# HM-RC-8_Remote-v02-010.net
KiCad netlist of a schematic drawn in EAGLE
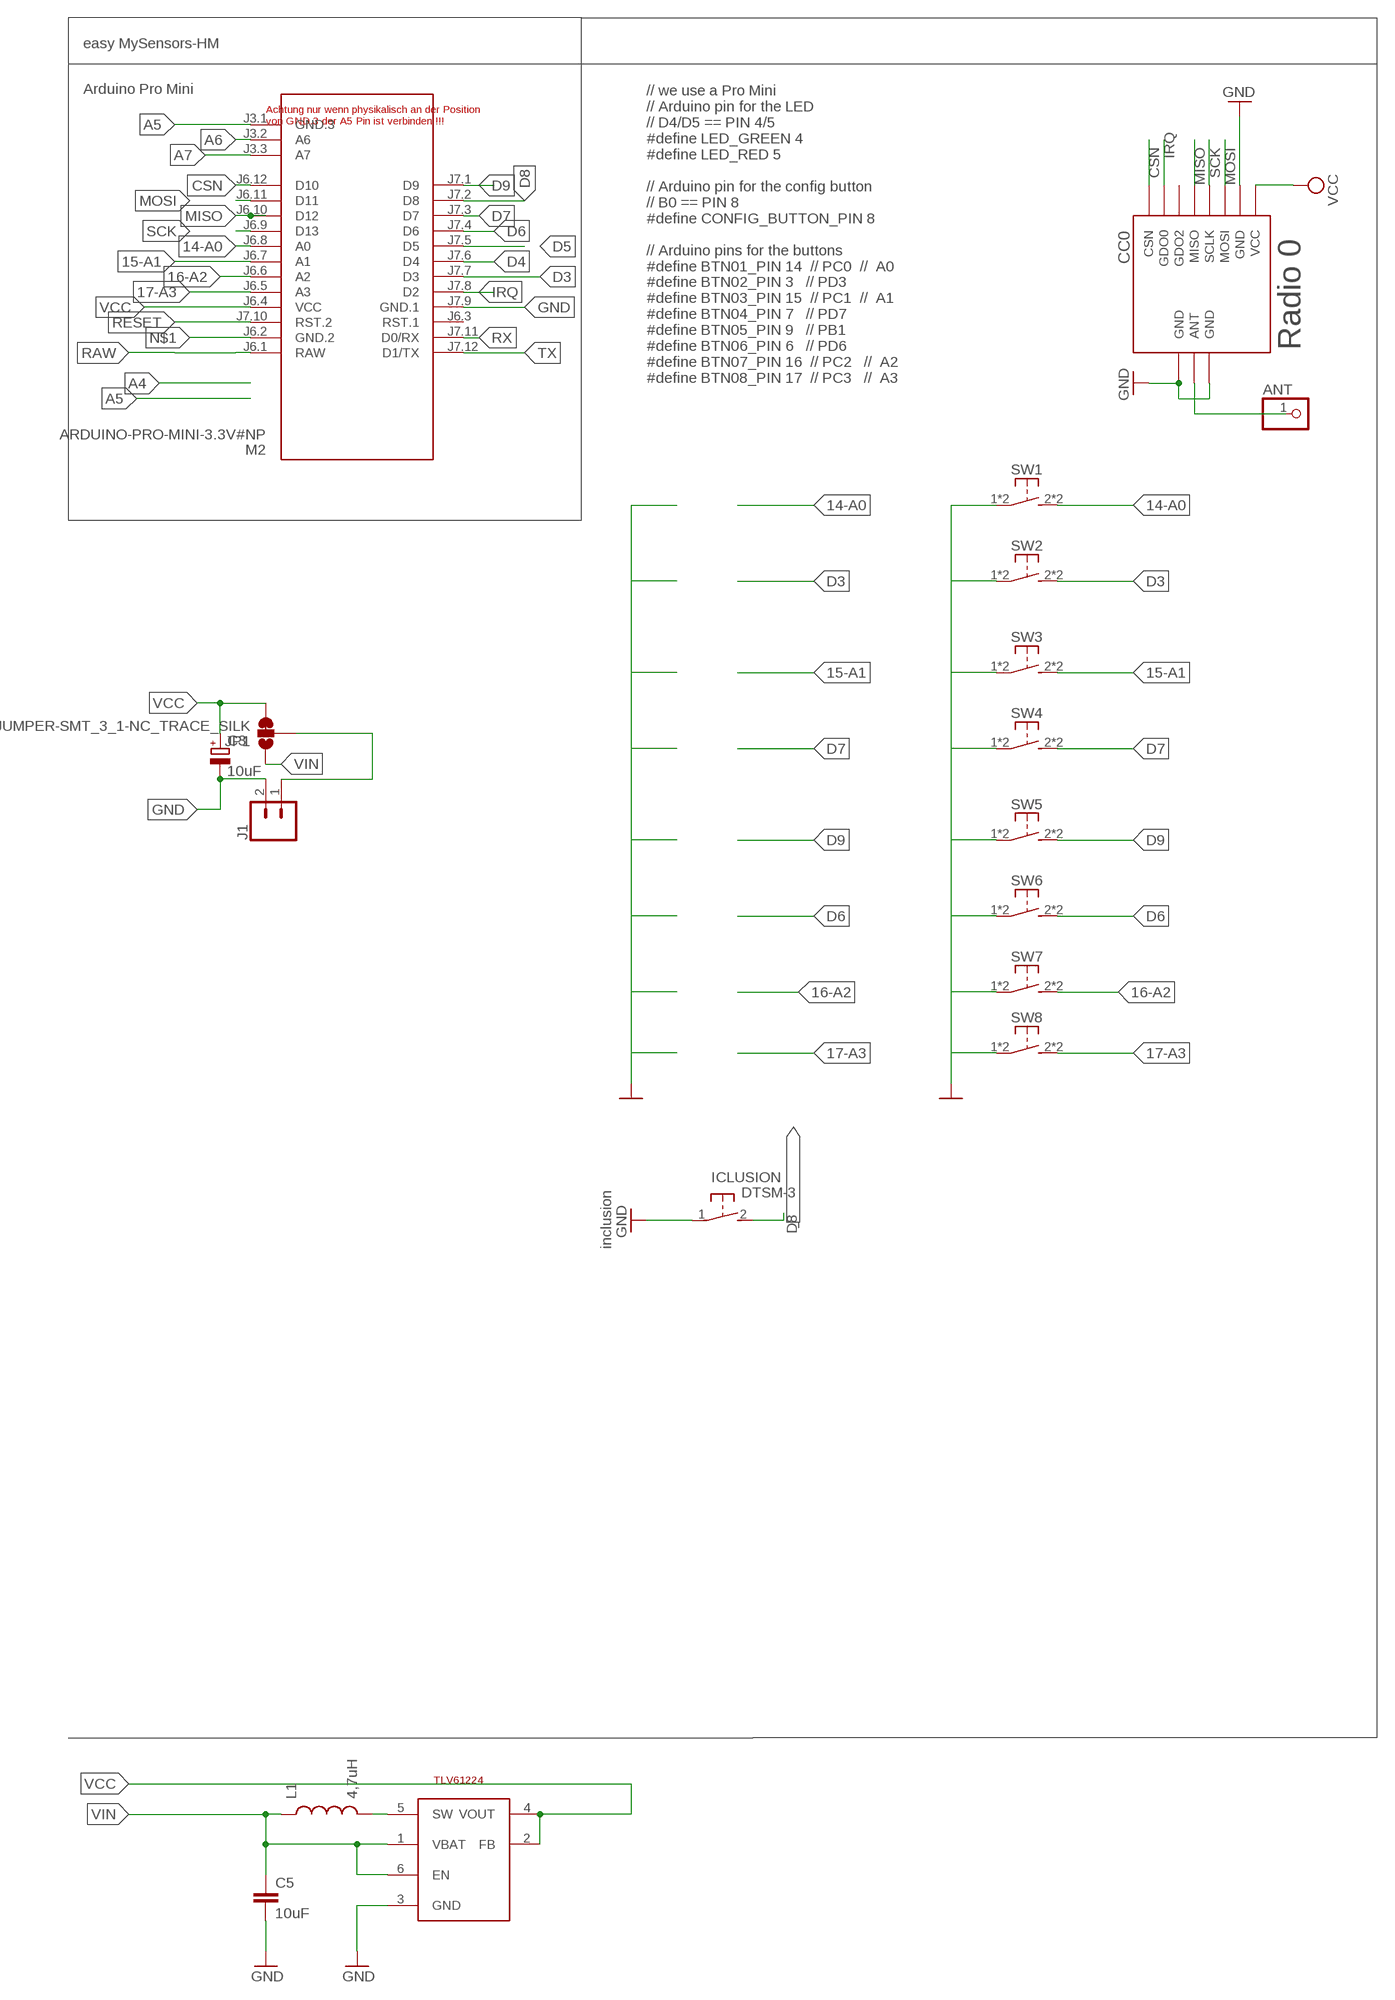
[diagram p0: schematic, sheet 1]

(export (version "E")
  (design (tool "Eeschema 10.0.6"))
  (components
    (comp (ref "ANT")
      (value "PINHD-1X1")
      (footprint "eagle-import:1X01")
      (libsource (lib "eagle-import") (part "PINHD-1X1"))
    )
    (comp (ref "C3")
      (value "10uF")
      (footprint "eagle-import:SMC_C")
      (libsource (lib "eagle-import") (part "CPOL-EUSMCC"))
    )
    (comp (ref "C5")
      (value "10uF")
      (footprint "eagle-import:0805")
      (libsource (lib "eagle-import") (part "CAP0805"))
    )
    (comp (ref "CC0")
      (value "CC1101")
      (footprint "eagle-import:CC1101_MODULE1_SMD")
      (libsource (lib "eagle-import") (part "CC1101_MODULE1SMD"))
    )
    (comp (ref "ICLUSION")
      (value "DTSM-3")
      (footprint "eagle-import:DTSM-3")
      (libsource (lib "eagle-import") (part "DTSM-3"))
    )
    (comp (ref "J1")
      (value "CONN_02PTH3")
      (footprint "eagle-import:1X02_LONGPADS")
      (libsource (lib "eagle-import") (part "CONN_02PTH3"))
    )
    (comp (ref "JP1")
      (value "JUMPER-SMT_3_1-NC_TRACE_SILK")
      (footprint "eagle-import:SMT-JUMPER_3_1-NC_TRACE_SILK")
      (libsource (lib "eagle-import") (part "JUMPER-SMT_3_1-NC_TRACE_SILK"))
    )
    (comp (ref "L1")
      (value "4,7uH")
      (footprint "eagle-import:0805")
      (libsource (lib "eagle-import") (part "INDUCTOR0805"))
    )
    (comp (ref "M2")
      (value "ARDUINO-PRO-MINI-3.3V#NP")
      (footprint "eagle-import:ARDUINO-PRO-MINI#NP")
      (libsource (lib "eagle-import") (part "ARDUINO-PRO-MINI-#NP3.3V"))
    )
    (comp (ref "STEPUP")
      (value "TLV61224")
      (footprint "eagle-import:SOT23-6L")
      (libsource (lib "eagle-import") (part "TI-TLV61224"))
    )
    (comp (ref "SW1")
      (value "SW-TACTILE-TL3305")
      (footprint "eagle-import:TL3305")
      (libsource (lib "eagle-import") (part "SW-TACTILE-TL3305"))
    )
    (comp (ref "SW2")
      (value "SW-TACTILE-TL3305")
      (footprint "eagle-import:TL3305")
      (libsource (lib "eagle-import") (part "SW-TACTILE-TL3305"))
    )
    (comp (ref "SW3")
      (value "SW-TACTILE-TL3305")
      (footprint "eagle-import:TL3305")
      (libsource (lib "eagle-import") (part "SW-TACTILE-TL3305"))
    )
    (comp (ref "SW4")
      (value "SW-TACTILE-TL3305")
      (footprint "eagle-import:TL3305")
      (libsource (lib "eagle-import") (part "SW-TACTILE-TL3305"))
    )
    (comp (ref "SW5")
      (value "SW-TACTILE-TL3305")
      (footprint "eagle-import:TL3305")
      (libsource (lib "eagle-import") (part "SW-TACTILE-TL3305"))
    )
    (comp (ref "SW6")
      (value "SW-TACTILE-TL3305")
      (footprint "eagle-import:TL3305")
      (libsource (lib "eagle-import") (part "SW-TACTILE-TL3305"))
    )
    (comp (ref "SW7")
      (value "SW-TACTILE-TL3305")
      (footprint "eagle-import:TL3305")
      (libsource (lib "eagle-import") (part "SW-TACTILE-TL3305"))
    )
    (comp (ref "SW8")
      (value "SW-TACTILE-TL3305")
      (footprint "eagle-import:TL3305")
      (libsource (lib "eagle-import") (part "SW-TACTILE-TL3305"))
    )
  )
  (nets
    (net (code "1") (name "14-A0") (class "Default")
      (node (ref "M2") (pin "J6.8") (pinfunction "A0_J6.8") (pintype "bidirectional"))
      (node (ref "SW1") (pin "2") (pinfunction "S1_2") (pintype "passive"))
      (node (ref "SW1") (pin "3") (pinfunction "S1_3") (pintype "passive"))
    )
    (net (code "2") (name "15-A1") (class "Default")
      (node (ref "M2") (pin "J6.7") (pinfunction "A1_J6.7") (pintype "bidirectional"))
      (node (ref "SW3") (pin "2") (pinfunction "S1_2") (pintype "passive"))
      (node (ref "SW3") (pin "3") (pinfunction "S1_3") (pintype "passive"))
    )
    (net (code "3") (name "16-A2") (class "Default")
      (node (ref "M2") (pin "J6.6") (pinfunction "A2_J6.6") (pintype "bidirectional"))
      (node (ref "SW7") (pin "2") (pinfunction "S1_2") (pintype "passive"))
      (node (ref "SW7") (pin "3") (pinfunction "S1_3") (pintype "passive"))
    )
    (net (code "4") (name "17-A3") (class "Default")
      (node (ref "M2") (pin "J6.5") (pinfunction "A3_J6.5") (pintype "bidirectional"))
      (node (ref "SW8") (pin "2") (pinfunction "S1_2") (pintype "passive"))
      (node (ref "SW8") (pin "3") (pinfunction "S1_3") (pintype "passive"))
    )
    (net (code "6") (name "A5") (class "Default")
      (node (ref "M2") (pin "J3.1") (pinfunction "GND.3_J3.1") (pintype "bidirectional"))
    )
    (net (code "7") (name "A6") (class "Default")
      (node (ref "M2") (pin "J3.2") (pinfunction "A6_J3.2") (pintype "bidirectional"))
    )
    (net (code "8") (name "A7") (class "Default")
      (node (ref "M2") (pin "J3.3") (pinfunction "A7_J3.3") (pintype "bidirectional"))
    )
    (net (code "9") (name "CSN") (class "Default")
      (node (ref "CC0") (pin "CSN") (pinfunction "CSN_CSN") (pintype "bidirectional"))
      (node (ref "M2") (pin "J6.12") (pinfunction "D10_J6.12") (pintype "bidirectional"))
    )
    (net (code "10") (name "D3") (class "Default")
      (node (ref "M2") (pin "J7.7") (pinfunction "D3_J7.7") (pintype "bidirectional"))
      (node (ref "SW2") (pin "2") (pinfunction "S1_2") (pintype "passive"))
      (node (ref "SW2") (pin "3") (pinfunction "S1_3") (pintype "passive"))
    )
    (net (code "11") (name "D4") (class "Default")
      (node (ref "M2") (pin "J7.6") (pinfunction "D4_J7.6") (pintype "bidirectional"))
    )
    (net (code "12") (name "D5") (class "Default")
      (node (ref "M2") (pin "J7.5") (pinfunction "D5_J7.5") (pintype "bidirectional"))
    )
    (net (code "13") (name "D6") (class "Default")
      (node (ref "M2") (pin "J7.4") (pinfunction "D6_J7.4") (pintype "bidirectional"))
      (node (ref "SW6") (pin "2") (pinfunction "S1_2") (pintype "passive"))
      (node (ref "SW6") (pin "3") (pinfunction "S1_3") (pintype "passive"))
    )
    (net (code "14") (name "D7") (class "Default")
      (node (ref "M2") (pin "J7.3") (pinfunction "D7_J7.3") (pintype "bidirectional"))
      (node (ref "SW4") (pin "2") (pinfunction "S1_2") (pintype "passive"))
      (node (ref "SW4") (pin "3") (pinfunction "S1_3") (pintype "passive"))
    )
    (net (code "15") (name "D8") (class "Default")
      (node (ref "ICLUSION") (pin "2") (pinfunction "2_2") (pintype "passive"))
      (node (ref "M2") (pin "J7.2") (pinfunction "D8_J7.2") (pintype "bidirectional"))
    )
    (net (code "16") (name "D9") (class "Default")
      (node (ref "M2") (pin "J7.1") (pinfunction "D9_J7.1") (pintype "bidirectional"))
      (node (ref "SW5") (pin "2") (pinfunction "S1_2") (pintype "passive"))
      (node (ref "SW5") (pin "3") (pinfunction "S1_3") (pintype "passive"))
    )
    (net (code "17") (name "GND") (class "Default")
      (node (ref "C3") (pin "-") (pinfunction "-_-") (pintype "passive"))
      (node (ref "C5") (pin "2") (pinfunction "2_2") (pintype "passive"))
      (node (ref "CC0") (pin "GND@0") (pinfunction "GND_GND@0") (pintype "power_in"))
      (node (ref "CC0") (pin "GND@1") (pinfunction "GND_GND@1") (pintype "power_in"))
      (node (ref "CC0") (pin "GND@2") (pinfunction "GND_GND@2") (pintype "power_in"))
      (node (ref "ICLUSION") (pin "1") (pinfunction "1_1") (pintype "passive"))
      (node (ref "J1") (pin "2") (pinfunction "2_2") (pintype "passive"))
      (node (ref "M2") (pin "J7.9") (pinfunction "GND.1_J7.9") (pintype "power_in"))
      (node (ref "STEPUP") (pin "3") (pinfunction "GND_3") (pintype "power_in"))
      (node (ref "SW1") (pin "1") (pinfunction "P1_1") (pintype "passive"))
      (node (ref "SW1") (pin "4") (pinfunction "P1_4") (pintype "passive"))
      (node (ref "SW3") (pin "1") (pinfunction "P1_1") (pintype "passive"))
      (node (ref "SW3") (pin "4") (pinfunction "P1_4") (pintype "passive"))
      (node (ref "SW4") (pin "1") (pinfunction "P1_1") (pintype "passive"))
      (node (ref "SW4") (pin "4") (pinfunction "P1_4") (pintype "passive"))
      (node (ref "SW5") (pin "1") (pinfunction "P1_1") (pintype "passive"))
      (node (ref "SW5") (pin "4") (pinfunction "P1_4") (pintype "passive"))
      (node (ref "SW6") (pin "1") (pinfunction "P1_1") (pintype "passive"))
      (node (ref "SW6") (pin "4") (pinfunction "P1_4") (pintype "passive"))
      (node (ref "SW7") (pin "1") (pinfunction "P1_1") (pintype "passive"))
      (node (ref "SW7") (pin "4") (pinfunction "P1_4") (pintype "passive"))
      (node (ref "SW8") (pin "1") (pinfunction "P1_1") (pintype "passive"))
      (node (ref "SW8") (pin "4") (pinfunction "P1_4") (pintype "passive"))
    )
    (net (code "18") (name "IRQ") (class "Default")
      (node (ref "CC0") (pin "GDO0") (pinfunction "GDO0_GDO0") (pintype "bidirectional"))
      (node (ref "M2") (pin "J7.8") (pinfunction "D2_J7.8") (pintype "bidirectional"))
    )
    (net (code "19") (name "MISO") (class "Default")
      (node (ref "CC0") (pin "MISO") (pinfunction "MISO_MISO") (pintype "bidirectional"))
      (node (ref "M2") (pin "J6.10") (pinfunction "D12_J6.10") (pintype "bidirectional"))
    )
    (net (code "20") (name "MOSI") (class "Default")
      (node (ref "CC0") (pin "MOSI") (pinfunction "MOSI_MOSI") (pintype "bidirectional"))
      (node (ref "M2") (pin "J6.11") (pinfunction "D11_J6.11") (pintype "bidirectional"))
    )
    (net (code "21") (name "N$1") (class "Default")
      (node (ref "M2") (pin "J6.2") (pinfunction "GND.2_J6.2") (pintype "power_in"))
    )
    (net (code "22") (name "Net-(ANT-Pad1)") (class "Default")
      (node (ref "ANT") (pin "1") (pinfunction "1_1") (pintype "passive"))
      (node (ref "CC0") (pin "ANT") (pinfunction "ANT_ANT") (pintype "output"))
    )
    (net (code "23") (name "Net-(J1-Pad1)") (class "Default")
      (node (ref "J1") (pin "1") (pinfunction "1_1") (pintype "passive"))
      (node (ref "JP1") (pin "2") (pinfunction "2_2") (pintype "passive"))
    )
    (net (code "24") (name "Net-(STEPUP-SW)") (class "Default")
      (node (ref "L1") (pin "2") (pinfunction "2_2") (pintype "passive"))
      (node (ref "STEPUP") (pin "5") (pinfunction "SW_5") (pintype "power_in"))
    )
    (net (code "25") (name "Net-(SW2-P1-Pad1)") (class "Default")
      (node (ref "SW2") (pin "1") (pinfunction "P1_1") (pintype "passive"))
      (node (ref "SW2") (pin "4") (pinfunction "P1_4") (pintype "passive"))
    )
    (net (code "26") (name "RAW") (class "Default")
      (node (ref "M2") (pin "J6.1") (pinfunction "RAW_J6.1") (pintype "power_in"))
    )
    (net (code "27") (name "RESET") (class "Default")
      (node (ref "M2") (pin "J7.10") (pinfunction "RST.2_J7.10") (pintype "bidirectional"))
    )
    (net (code "28") (name "RX") (class "Default")
      (node (ref "M2") (pin "J7.11") (pinfunction "D0/RX_J7.11") (pintype "bidirectional"))
    )
    (net (code "29") (name "SCK") (class "Default")
      (node (ref "CC0") (pin "SCLK") (pinfunction "SCLK_SCLK") (pintype "bidirectional"))
      (node (ref "M2") (pin "J6.9") (pinfunction "D13_J6.9") (pintype "bidirectional"))
    )
    (net (code "30") (name "TX") (class "Default")
      (node (ref "M2") (pin "J7.12") (pinfunction "D1/TX_J7.12") (pintype "bidirectional"))
    )
    (net (code "31") (name "VCC") (class "Default")
      (node (ref "C3") (pin "+") (pinfunction "+_+") (pintype "passive"))
      (node (ref "CC0") (pin "VCC") (pinfunction "VCC_VCC") (pintype "power_in"))
      (node (ref "JP1") (pin "3") (pinfunction "3_3") (pintype "passive"))
      (node (ref "M2") (pin "J6.4") (pinfunction "VCC_J6.4") (pintype "power_in"))
      (node (ref "STEPUP") (pin "2") (pinfunction "FB_2") (pintype "input"))
      (node (ref "STEPUP") (pin "4") (pinfunction "VOUT_4") (pintype "power_in"))
    )
    (net (code "32") (name "VIN") (class "Default")
      (node (ref "C5") (pin "1") (pinfunction "1_1") (pintype "passive"))
      (node (ref "JP1") (pin "1") (pinfunction "1_1") (pintype "passive"))
      (node (ref "L1") (pin "1") (pinfunction "1_1") (pintype "passive"))
      (node (ref "STEPUP") (pin "1") (pinfunction "VBAT_1") (pintype "power_in"))
      (node (ref "STEPUP") (pin "6") (pinfunction "EN_6") (pintype "input"))
    )
    (net (code "33") (name "unconnected-(CC0-PadGDO2)") (class "Default")
      (node (ref "CC0") (pin "GDO2") (pinfunction "GDO2_GDO2") (pintype "bidirectional"))
    )
    (net (code "34") (name "unconnected-(M2-RST.1-PadJ6.3)") (class "Default")
      (node (ref "M2") (pin "J6.3") (pinfunction "RST.1_J6.3") (pintype "bidirectional"))
    )
  )
)
